# 2_-_Connector_Page.net
KiCad netlist of a schematic drawn in Altium Designer
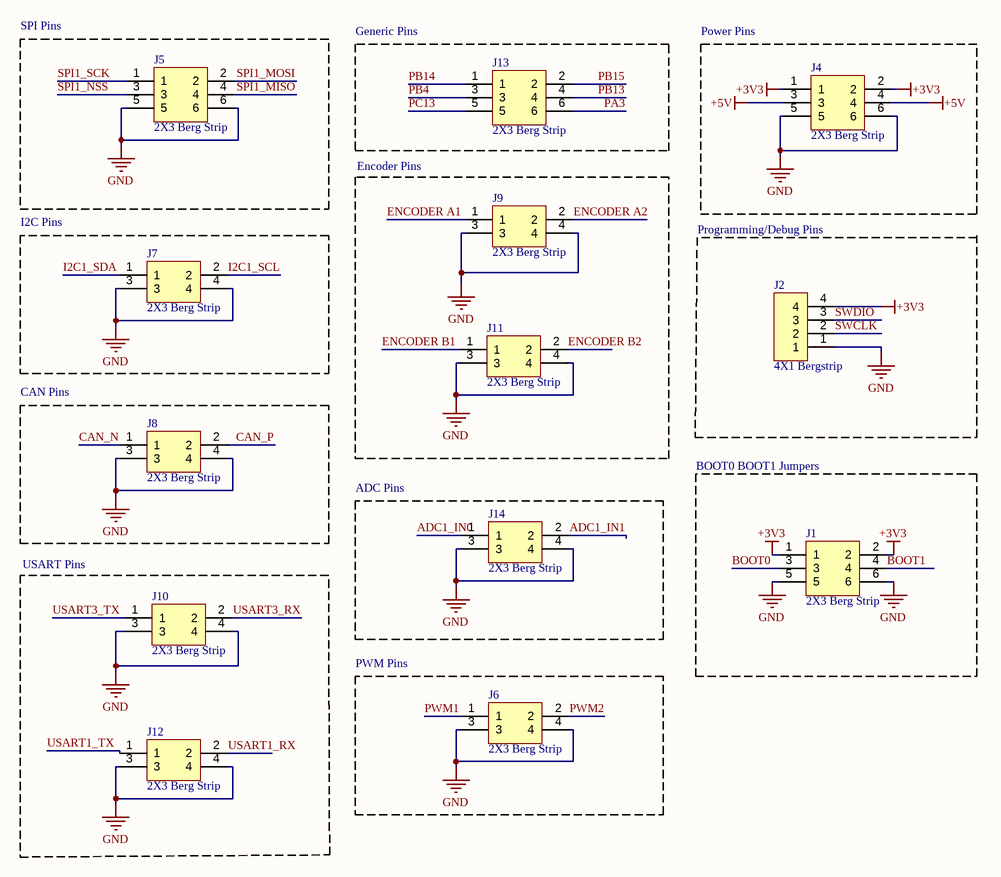
[diagram p0: [2]- Connector_Page.SchDoc]

(export (version "E")
  (design (tool "Eeschema 10.0.6"))
  (components
    (comp (ref "J1")
      (value "2X3 Berg Strip")
      (footprint "CON6_100_59D78_TH_ST_Duplicate")
      (description "6 pin, 2 row, 2.54mm pitch bergstrip")
      (fields (field (name "MANUFACTURER") "NA"))
      (libsource (lib "STM_SCH_LIB") (part "CON-BS-PLG_2X3-100-TH-ST"))
    )
    (comp (ref "J2")
      (value "4X1 Bergstrip")
      (footprint "CON4_100_40D72_TH_ST_MALE")
      (description "4 pin, 1 row, 2.54mm pitch bergstrip")
      (fields (field (name "MANUFACTURER") "NA"))
      (libsource (lib "STM_SCH_LIB") (part "CON-BS-PLG_4X1-100-TH-ST"))
    )
    (comp (ref "J4")
      (value "2X3 Berg Strip")
      (footprint "CON6_100_59D78_TH_ST_Duplicate")
      (description "6 pin, 2 row, 2.54mm pitch bergstrip")
      (fields (field (name "MANUFACTURER") "NA"))
      (libsource (lib "STM_SCH_LIB") (part "CON-BS-PLG_2X3-100-TH-ST"))
    )
    (comp (ref "J5")
      (value "2X3 Berg Strip")
      (footprint "CON6_100_59D78_TH_ST_Duplicate")
      (description "6 pin, 2 row, 2.54mm pitch bergstrip")
      (fields (field (name "MANUFACTURER") "NA"))
      (libsource (lib "STM_SCH_LIB") (part "CON-BS-PLG_2X3-100-TH-ST"))
    )
    (comp (ref "J6")
      (value "2X3 Berg Strip")
      (footprint "CON4_100_59D78_TH_ST_Duplicate")
      (description "4 pin, 2 row, 2.54mm pitch bergstrip")
      (libsource (lib "STM_SCH_LIB") (part "CON-BS-PLG_2X2-100-TH-ST"))
    )
    (comp (ref "J7")
      (value "2X3 Berg Strip")
      (footprint "CON4_100_59D78_TH_ST_Duplicate")
      (description "4 pin, 2 row, 2.54mm pitch bergstrip")
      (libsource (lib "STM_SCH_LIB") (part "CON-BS-PLG_2X2-100-TH-ST"))
    )
    (comp (ref "J8")
      (value "2X3 Berg Strip")
      (footprint "CON4_100_59D78_TH_ST_Duplicate")
      (description "4 pin, 2 row, 2.54mm pitch bergstrip")
      (libsource (lib "STM_SCH_LIB") (part "CON-BS-PLG_2X2-100-TH-ST"))
    )
    (comp (ref "J9")
      (value "2X3 Berg Strip")
      (footprint "CON4_100_59D78_TH_ST_Duplicate")
      (description "4 pin, 2 row, 2.54mm pitch bergstrip")
      (libsource (lib "STM_SCH_LIB") (part "CON-BS-PLG_2X2-100-TH-ST"))
    )
    (comp (ref "J10")
      (value "2X3 Berg Strip")
      (footprint "CON4_100_59D78_TH_ST_Duplicate")
      (description "4 pin, 2 row, 2.54mm pitch bergstrip")
      (libsource (lib "STM_SCH_LIB") (part "CON-BS-PLG_2X2-100-TH-ST"))
    )
    (comp (ref "J11")
      (value "2X3 Berg Strip")
      (footprint "CON4_100_59D78_TH_ST_Duplicate")
      (description "4 pin, 2 row, 2.54mm pitch bergstrip")
      (libsource (lib "STM_SCH_LIB") (part "CON-BS-PLG_2X2-100-TH-ST"))
    )
    (comp (ref "J12")
      (value "2X3 Berg Strip")
      (footprint "CON4_100_59D78_TH_ST_Duplicate")
      (description "4 pin, 2 row, 2.54mm pitch bergstrip")
      (libsource (lib "STM_SCH_LIB") (part "CON-BS-PLG_2X2-100-TH-ST"))
    )
    (comp (ref "J13")
      (value "2X3 Berg Strip")
      (footprint "CON6_100_59D78_TH_ST_Duplicate")
      (description "6 pin, 2 row, 2.54mm pitch bergstrip")
      (fields (field (name "MANUFACTURER") "NA"))
      (libsource (lib "STM_SCH_LIB") (part "CON-BS-PLG_2X3-100-TH-ST"))
    )
    (comp (ref "J14")
      (value "2X3 Berg Strip")
      (footprint "CON4_100_59D78_TH_ST_Duplicate")
      (description "4 pin, 2 row, 2.54mm pitch bergstrip")
      (libsource (lib "STM_SCH_LIB") (part "CON-BS-PLG_2X2-100-TH-ST"))
    )
  )
  (nets
    (net (code "1") (name "+3V3") (class "Default")
      (node (ref "J1") (pin "1") (pinfunction "1_1") (pintype "passive"))
      (node (ref "J1") (pin "2") (pinfunction "2_2") (pintype "passive"))
      (node (ref "J2") (pin "4") (pinfunction "4_4") (pintype "passive"))
      (node (ref "J4") (pin "1") (pinfunction "1_1") (pintype "passive"))
      (node (ref "J4") (pin "2") (pinfunction "2_2") (pintype "passive"))
    )
    (net (code "2") (name "+5V") (class "Default")
      (node (ref "J4") (pin "3") (pinfunction "3_3") (pintype "passive"))
      (node (ref "J4") (pin "4") (pinfunction "4_4") (pintype "passive"))
    )
    (net (code "3") (name "/ADC1_IN0") (class "Default")
      (node (ref "J14") (pin "1") (pinfunction "1_1") (pintype "passive"))
    )
    (net (code "4") (name "/ADC1_IN1") (class "Default")
      (node (ref "J14") (pin "2") (pinfunction "2_2") (pintype "passive"))
    )
    (net (code "5") (name "/BOOT0") (class "Default")
      (node (ref "J1") (pin "3") (pinfunction "3_3") (pintype "passive"))
    )
    (net (code "6") (name "/BOOT1") (class "Default")
      (node (ref "J1") (pin "4") (pinfunction "4_4") (pintype "passive"))
    )
    (net (code "7") (name "/CAN_N") (class "Default")
      (node (ref "J8") (pin "1") (pinfunction "1_1") (pintype "passive"))
    )
    (net (code "8") (name "/CAN_P") (class "Default")
      (node (ref "J8") (pin "2") (pinfunction "2_2") (pintype "passive"))
    )
    (net (code "9") (name "/ENCODER A1") (class "Default")
      (node (ref "J9") (pin "1") (pinfunction "1_1") (pintype "passive"))
    )
    (net (code "10") (name "/ENCODER A2") (class "Default")
      (node (ref "J9") (pin "2") (pinfunction "2_2") (pintype "passive"))
    )
    (net (code "11") (name "/ENCODER B1") (class "Default")
      (node (ref "J11") (pin "1") (pinfunction "1_1") (pintype "passive"))
    )
    (net (code "12") (name "/ENCODER B2") (class "Default")
      (node (ref "J11") (pin "2") (pinfunction "2_2") (pintype "passive"))
    )
    (net (code "13") (name "/I2C1_SCL") (class "Default")
      (node (ref "J7") (pin "2") (pinfunction "2_2") (pintype "passive"))
    )
    (net (code "14") (name "/I2C1_SDA") (class "Default")
      (node (ref "J7") (pin "1") (pinfunction "1_1") (pintype "passive"))
    )
    (net (code "15") (name "/PA3") (class "Default")
      (node (ref "J13") (pin "6") (pinfunction "6_6") (pintype "passive"))
    )
    (net (code "16") (name "/PB4") (class "Default")
      (node (ref "J13") (pin "3") (pinfunction "3_3") (pintype "passive"))
    )
    (net (code "17") (name "/PB13") (class "Default")
      (node (ref "J13") (pin "4") (pinfunction "4_4") (pintype "passive"))
    )
    (net (code "18") (name "/PB14") (class "Default")
      (node (ref "J13") (pin "1") (pinfunction "1_1") (pintype "passive"))
    )
    (net (code "19") (name "/PB15") (class "Default")
      (node (ref "J13") (pin "2") (pinfunction "2_2") (pintype "passive"))
    )
    (net (code "20") (name "/PC13") (class "Default")
      (node (ref "J13") (pin "5") (pinfunction "5_5") (pintype "passive"))
    )
    (net (code "21") (name "/PWM1") (class "Default")
      (node (ref "J6") (pin "1") (pinfunction "1_1") (pintype "passive"))
    )
    (net (code "22") (name "/PWM2") (class "Default")
      (node (ref "J6") (pin "2") (pinfunction "2_2") (pintype "passive"))
    )
    (net (code "23") (name "/SPI1_MISO") (class "Default")
      (node (ref "J5") (pin "4") (pinfunction "4_4") (pintype "passive"))
    )
    (net (code "24") (name "/SPI1_MOSI") (class "Default")
      (node (ref "J5") (pin "2") (pinfunction "2_2") (pintype "passive"))
    )
    (net (code "25") (name "/SPI1_NSS") (class "Default")
      (node (ref "J5") (pin "3") (pinfunction "3_3") (pintype "passive"))
    )
    (net (code "26") (name "/SPI1_SCK") (class "Default")
      (node (ref "J5") (pin "1") (pinfunction "1_1") (pintype "passive"))
    )
    (net (code "27") (name "/SWCLK") (class "Default")
      (node (ref "J2") (pin "2") (pinfunction "2_2") (pintype "passive"))
    )
    (net (code "28") (name "/SWDIO") (class "Default")
      (node (ref "J2") (pin "3") (pinfunction "3_3") (pintype "passive"))
    )
    (net (code "29") (name "/USART1_RX") (class "Default")
      (node (ref "J12") (pin "2") (pinfunction "2_2") (pintype "passive"))
    )
    (net (code "30") (name "/USART1_TX") (class "Default")
      (node (ref "J12") (pin "1") (pinfunction "1_1") (pintype "passive"))
    )
    (net (code "31") (name "/USART3_RX") (class "Default")
      (node (ref "J10") (pin "2") (pinfunction "2_2") (pintype "passive"))
    )
    (net (code "32") (name "/USART3_TX") (class "Default")
      (node (ref "J10") (pin "1") (pinfunction "1_1") (pintype "passive"))
    )
    (net (code "33") (name "GND") (class "Default")
      (node (ref "J1") (pin "5") (pinfunction "5_5") (pintype "passive"))
      (node (ref "J1") (pin "6") (pinfunction "6_6") (pintype "passive"))
      (node (ref "J10") (pin "3") (pinfunction "3_3") (pintype "passive"))
      (node (ref "J10") (pin "4") (pinfunction "4_4") (pintype "passive"))
      (node (ref "J11") (pin "3") (pinfunction "3_3") (pintype "passive"))
      (node (ref "J11") (pin "4") (pinfunction "4_4") (pintype "passive"))
      (node (ref "J12") (pin "3") (pinfunction "3_3") (pintype "passive"))
      (node (ref "J12") (pin "4") (pinfunction "4_4") (pintype "passive"))
      (node (ref "J14") (pin "3") (pinfunction "3_3") (pintype "passive"))
      (node (ref "J14") (pin "4") (pinfunction "4_4") (pintype "passive"))
      (node (ref "J2") (pin "1") (pinfunction "1_1") (pintype "passive"))
      (node (ref "J4") (pin "5") (pinfunction "5_5") (pintype "passive"))
      (node (ref "J4") (pin "6") (pinfunction "6_6") (pintype "passive"))
      (node (ref "J5") (pin "5") (pinfunction "5_5") (pintype "passive"))
      (node (ref "J5") (pin "6") (pinfunction "6_6") (pintype "passive"))
      (node (ref "J6") (pin "3") (pinfunction "3_3") (pintype "passive"))
      (node (ref "J6") (pin "4") (pinfunction "4_4") (pintype "passive"))
      (node (ref "J7") (pin "3") (pinfunction "3_3") (pintype "passive"))
      (node (ref "J7") (pin "4") (pinfunction "4_4") (pintype "passive"))
      (node (ref "J8") (pin "3") (pinfunction "3_3") (pintype "passive"))
      (node (ref "J8") (pin "4") (pinfunction "4_4") (pintype "passive"))
      (node (ref "J9") (pin "3") (pinfunction "3_3") (pintype "passive"))
      (node (ref "J9") (pin "4") (pinfunction "4_4") (pintype "passive"))
    )
  )
)
